# Sheet1.net
KiCad netlist of a schematic drawn in Altium Designer
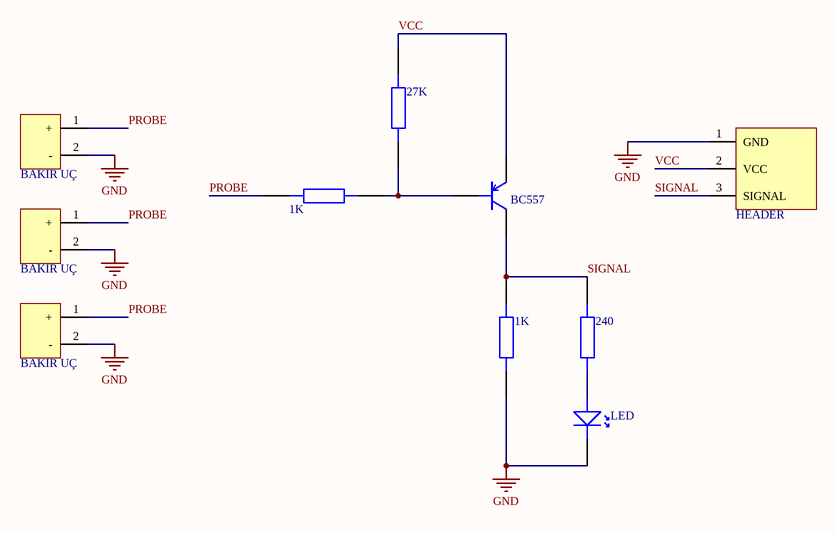
[diagram p0: Sheet1.SchDoc]

(export (version "E")
  (design (tool "Eeschema 10.0.6"))
  (components
    (comp (ref "D1") (value "LED") (footprint "LED") (libsource (lib "Schlib1") (part "LED")))
    (comp (ref "K1")
      (value "BAKIR UÇ")
      (footprint "KONNECTOR 2 PIN")
      (libsource (lib "Schlib1") (part "HEADER 2 PIN"))
    )
    (comp (ref "K2")
      (value "BAKIR UÇ")
      (footprint "KONNECTOR 2 PIN")
      (libsource (lib "Schlib1") (part "HEADER 2 PIN"))
    )
    (comp (ref "K3")
      (value "BAKIR UÇ")
      (footprint "KONNECTOR 2 PIN")
      (libsource (lib "Schlib1") (part "HEADER 2 PIN"))
    )
    (comp (ref "K4")
      (value "HEADER")
      (footprint "KONNECTOR 3 PIN")
      (libsource (lib "Schlib1") (part "HEADER 3 PIN"))
    )
    (comp (ref "R1") (value "1K") (footprint "RESISTOR") (libsource (lib "Schlib1") (part "RESISTOR")))
    (comp (ref "R2") (value "27K") (footprint "RESISTOR") (libsource (lib "Schlib1") (part "RESISTOR")))
    (comp (ref "R3") (value "1K") (footprint "RESISTOR") (libsource (lib "Schlib1") (part "RESISTOR")))
    (comp (ref "R4") (value "240") (footprint "RESISTOR") (libsource (lib "Schlib1") (part "RESISTOR")))
    (comp (ref "T1") (value "BC557") (footprint "TRANSİSTOR") (libsource (lib "Schlib1") (part "TRANSISTOR")))
  )
  (nets
    (net (code "1") (name "/PROBE") (class "Default")
      (node (ref "K1") (pin "1") (pinfunction "+_1") (pintype "passive"))
      (node (ref "K2") (pin "1") (pinfunction "+_1") (pintype "passive"))
      (node (ref "K3") (pin "1") (pinfunction "+_1") (pintype "passive"))
      (node (ref "R1") (pin "1") (pinfunction "1_1") (pintype "passive"))
    )
    (net (code "2") (name "/SIGNAL") (class "Default")
      (node (ref "K4") (pin "3") (pinfunction "SIGNAL_3") (pintype "passive"))
      (node (ref "R3") (pin "2") (pinfunction "2_2") (pintype "passive"))
      (node (ref "R4") (pin "2") (pinfunction "2_2") (pintype "passive"))
      (node (ref "T1") (pin "2") (pinfunction "2_2") (pintype "passive"))
    )
    (net (code "3") (name "/VCC") (class "Default")
      (node (ref "K4") (pin "2") (pinfunction "VCC_2") (pintype "passive"))
      (node (ref "R2") (pin "2") (pinfunction "2_2") (pintype "passive"))
      (node (ref "T1") (pin "3") (pinfunction "3_3") (pintype "passive"))
    )
    (net (code "4") (name "GND") (class "Default")
      (node (ref "D1") (pin "2") (pinfunction "2_2") (pintype "passive"))
      (node (ref "K1") (pin "2") (pinfunction "-_2") (pintype "passive"))
      (node (ref "K2") (pin "2") (pinfunction "-_2") (pintype "passive"))
      (node (ref "K3") (pin "2") (pinfunction "-_2") (pintype "passive"))
      (node (ref "K4") (pin "1") (pinfunction "GND_1") (pintype "passive"))
      (node (ref "R3") (pin "1") (pinfunction "1_1") (pintype "passive"))
    )
    (net (code "5") (name "Net-(D1-Pad1)") (class "Default")
      (node (ref "D1") (pin "1") (pinfunction "1_1") (pintype "passive"))
      (node (ref "R4") (pin "1") (pinfunction "1_1") (pintype "passive"))
    )
    (net (code "6") (name "Net-(R1-Pad2)") (class "Default")
      (node (ref "R1") (pin "2") (pinfunction "2_2") (pintype "passive"))
      (node (ref "R2") (pin "1") (pinfunction "1_1") (pintype "passive"))
      (node (ref "T1") (pin "1") (pinfunction "1_1") (pintype "passive"))
    )
  )
)
